# SoundKey.net
KiCad netlist of a schematic drawn in EAGLE
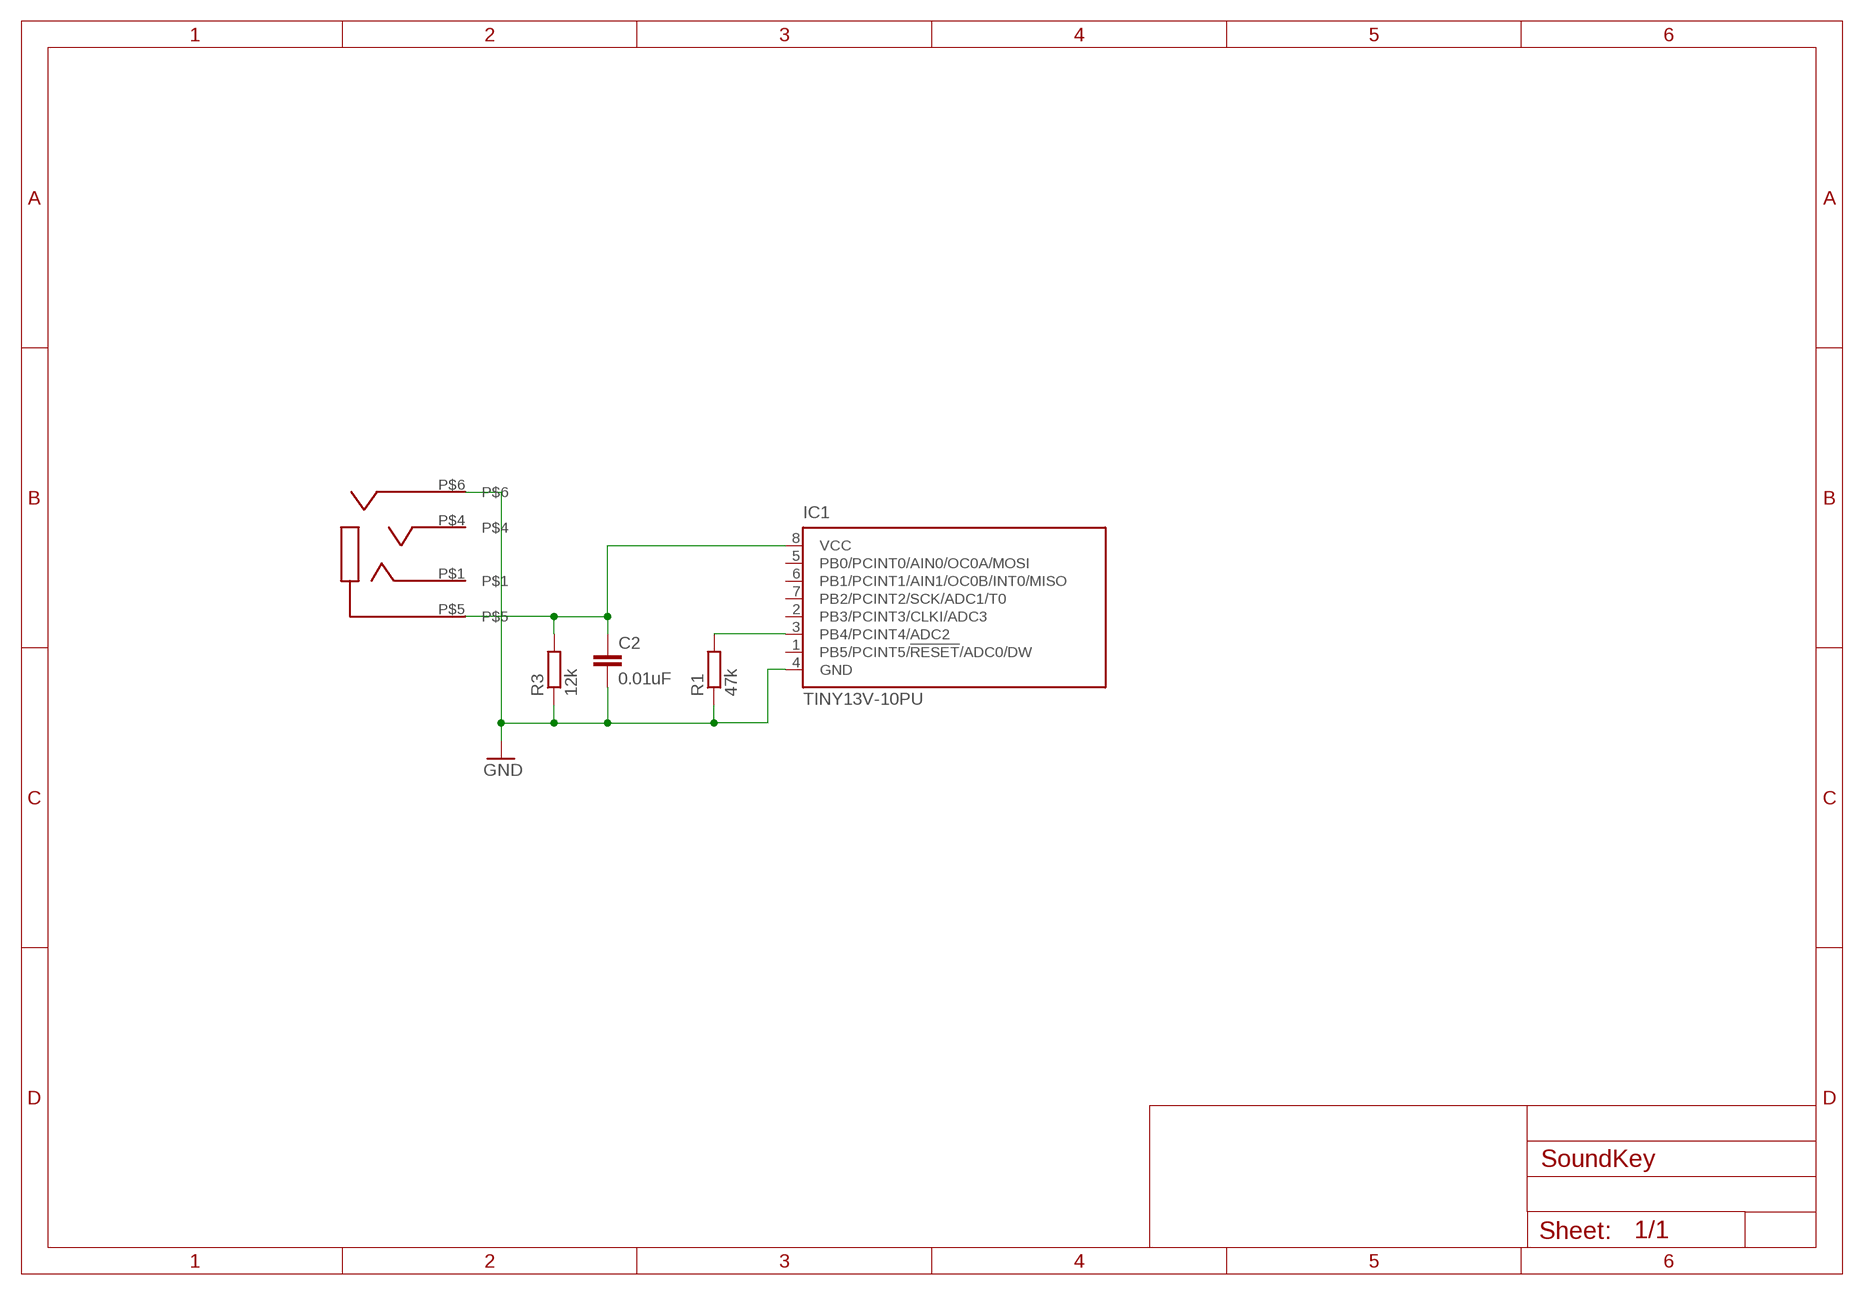
[diagram p0: schematic, sheet 1]

(export (version "E")
  (design (tool "Eeschema 10.0.6"))
  (components
    (comp (ref "C2")
      (value "0.01uF")
      (footprint "eagle-import:C025-030X050")
      (libsource (lib "eagle-import") (part "C-EU025-030X050"))
    )
    (comp (ref "IC1")
      (value "TINY13V-10PU")
      (footprint "eagle-import:DIL08")
      (fields (field (name "MPN") "ATTINY13V-10PU"))
      (libsource (lib "eagle-import") (part "TINY13PUV-10"))
    )
    (comp (ref "R1")
      (value "47k")
      (footprint "eagle-import:0207_10")
      (libsource (lib "eagle-import") (part "R-EU_0207/10"))
    )
    (comp (ref "R3")
      (value "12k")
      (footprint "eagle-import:0207_10")
      (libsource (lib "eagle-import") (part "R-EU_0207/10"))
    )
    (comp (ref "U$3")
      (value "SJ-43514")
      (footprint "eagle-import:SJ43514")
      (libsource (lib "eagle-import") (part "SJ-43514"))
    )
  )
  (nets
    (net (code "1") (name "GND") (class "Default")
      (node (ref "C2") (pin "2") (pinfunction "2_2") (pintype "passive"))
      (node (ref "IC1") (pin "4") (pinfunction "GND_4") (pintype "power_in"))
      (node (ref "R1") (pin "1") (pinfunction "1_1") (pintype "passive"))
      (node (ref "R3") (pin "1") (pinfunction "1_1") (pintype "passive"))
      (node (ref "U$3") (pin "P$6") (pinfunction "P$6_P$6") (pintype "bidirectional"))
    )
    (net (code "2") (name "Net-(IC1-PB4{slash}PCINT4{slash}ADC2)") (class "Default")
      (node (ref "IC1") (pin "3") (pinfunction "PB4/PCINT4/ADC2_3") (pintype "bidirectional"))
      (node (ref "R1") (pin "2") (pinfunction "2_2") (pintype "passive"))
    )
    (net (code "3") (name "Net-(IC1-VCC)") (class "Default")
      (node (ref "C2") (pin "1") (pinfunction "1_1") (pintype "passive"))
      (node (ref "IC1") (pin "8") (pinfunction "VCC_8") (pintype "power_in"))
      (node (ref "R3") (pin "2") (pinfunction "2_2") (pintype "passive"))
      (node (ref "U$3") (pin "P$5") (pinfunction "P$5_P$5") (pintype "bidirectional"))
    )
    (net (code "4") (name "unconnected-(IC1-PB0{slash}PCINT0{slash}AIN0{slash}OC0A{slash}MOSI-Pad5)") (class "Default")
      (node (ref "IC1") (pin "5") (pinfunction "PB0/PCINT0/AIN0/OC0A/MOSI_5") (pintype "bidirectional"))
    )
    (net (code "5") (name "unconnected-(IC1-PB1{slash}PCINT1{slash}AIN1{slash}OC0B{slash}INT0{slash}MISO-Pad6)") (class "Default")
      (node (ref "IC1") (pin "6") (pinfunction "PB1/PCINT1/AIN1/OC0B/INT0/MISO_6") (pintype "bidirectional"))
    )
    (net (code "6") (name "unconnected-(IC1-PB2{slash}PCINT2{slash}SCK{slash}ADC1{slash}T0-Pad7)") (class "Default")
      (node (ref "IC1") (pin "7") (pinfunction "PB2/PCINT2/SCK/ADC1/T0_7") (pintype "bidirectional"))
    )
    (net (code "7") (name "unconnected-(IC1-PB3{slash}PCINT3{slash}CLKI{slash}ADC3-Pad2)") (class "Default")
      (node (ref "IC1") (pin "2") (pinfunction "PB3/PCINT3/CLKI/ADC3_2") (pintype "bidirectional"))
    )
    (net (code "8") (name "unconnected-(IC1-PB5{slash}PCINT5{slash}~{RESET}{slash}ADC0{slash}DW-Pad1)") (class "Default")
      (node (ref "IC1") (pin "1") (pinfunction "PB5/PCINT5/~{RESET}/ADC0/DW_1") (pintype "bidirectional"))
    )
    (net (code "9") (name "unconnected-(U$3-PadP$1)") (class "Default")
      (node (ref "U$3") (pin "P$1") (pinfunction "P$1_P$1") (pintype "bidirectional"))
    )
    (net (code "10") (name "unconnected-(U$3-PadP$4)") (class "Default")
      (node (ref "U$3") (pin "P$4") (pinfunction "P$4_P$4") (pintype "bidirectional"))
    )
  )
)
